# Arduino-RedBoard_new.net
KiCad netlist of a schematic drawn in Altium Designer
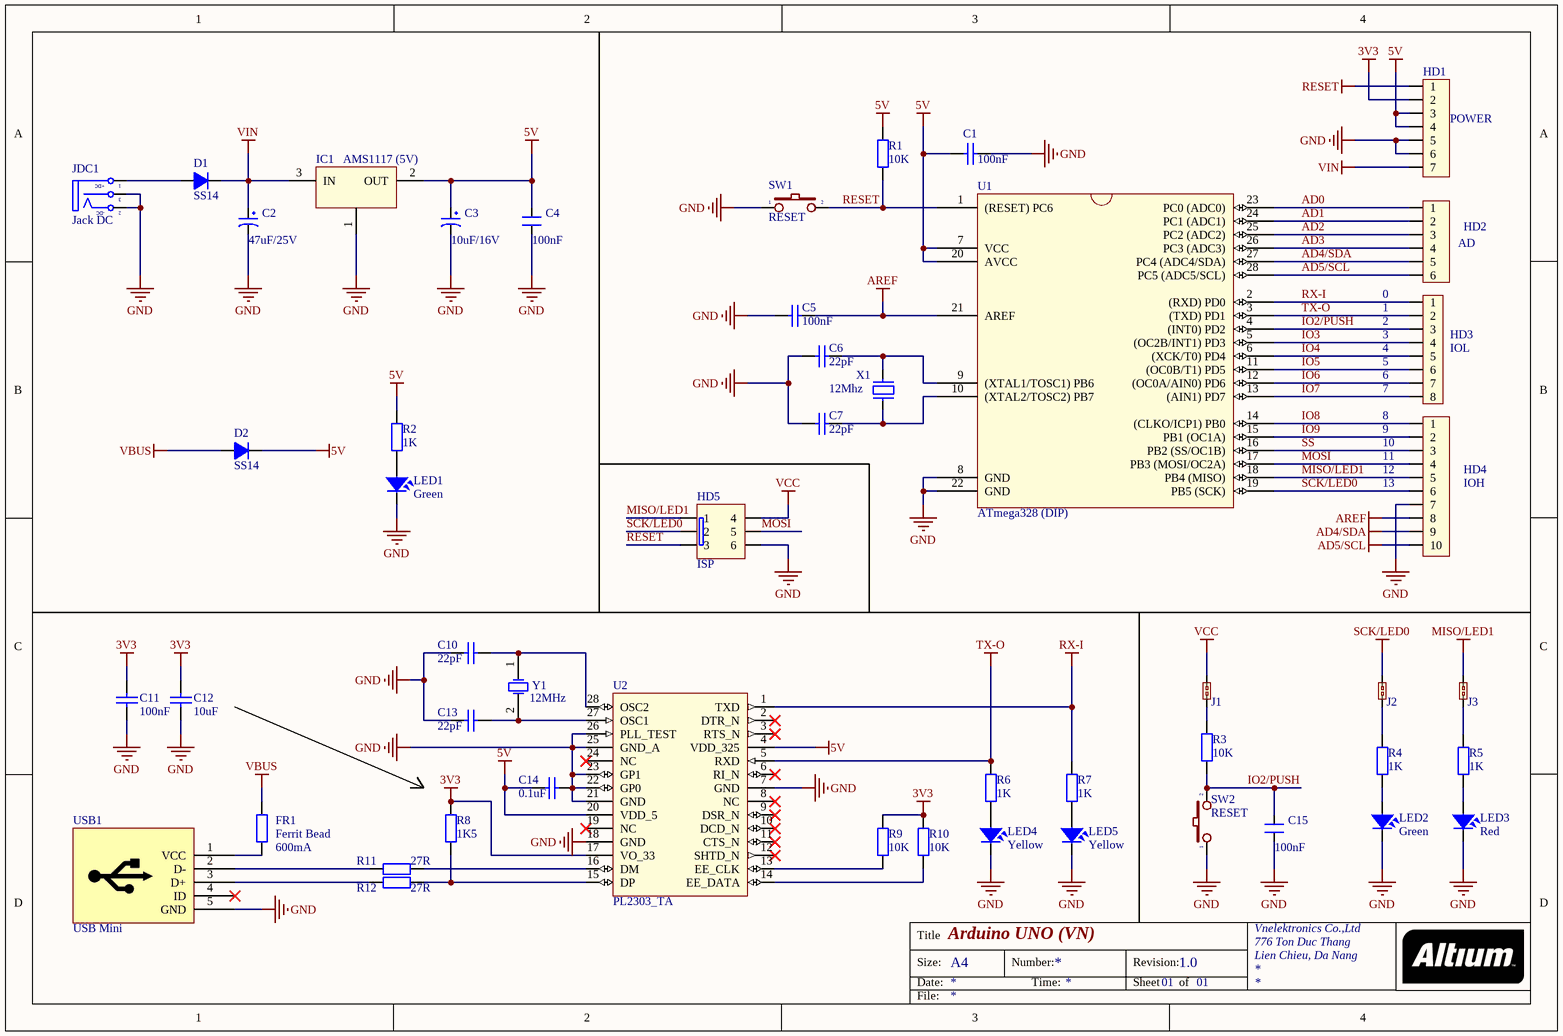
[diagram p0: Arduino-RedBoard_new.schdoc]

(export (version "E")
  (design (tool "Eeschema 10.0.6"))
  (components
    (comp (ref "C1")
      (value "100nF")
      (footprint "C0603")
      (description "CAP NPO CAPNTO 1nF 100V 10%")
      (fields (field (name "Comment") "5AK102KABAA"))
      (libsource (lib "lpson") (part "5AK102KABAA"))
    )
    (comp (ref "C2") (value "47uF/25V") (footprint "C_FK_47UF_25V") (libsource (lib "VNELEK") (part "CP1")))
    (comp (ref "C3")
      (value "10uF/16V")
      (footprint "C0805")
      (description "Cap P  0,1uF < 22uF , 16 - 50V")
      (libsource (lib "VNELEK") (part "CP1"))
    )
    (comp (ref "C4")
      (value "100nF")
      (footprint "C0603")
      (description "Cap np 104 => 105pF")
      (libsource (lib "VNELEK") (part "CN2"))
    )
    (comp (ref "C5")
      (value "100nF")
      (footprint "C0603")
      (description "CAP NPO CAPNTO 1nF 100V 10%")
      (fields (field (name "Comment") "5AK102KABAA"))
      (libsource (lib "lpson") (part "5AK102KABAA"))
    )
    (comp (ref "C6")
      (value "22pF")
      (footprint "C0603")
      (description "CAP NPO CAPNTO 1nF 100V 10%")
      (fields (field (name "Comment") "5AK102KABAA"))
      (libsource (lib "lpson") (part "5AK102KABAA"))
    )
    (comp (ref "C7")
      (value "22pF")
      (footprint "C0603")
      (description "CAP NPO CAPNTO 1nF 100V 10%")
      (fields (field (name "Comment") "5AK102KABAA"))
      (libsource (lib "lpson") (part "5AK102KABAA"))
    )
    (comp (ref "C10")
      (value "22pF")
      (footprint "C0603")
      (description "22pF/50V ±5% NPO SMD-0603 Capacitor")
      (fields (field (name "Comment") "CC0603JRNPO9BN") (field (name "PUBLISHER") "Altium Limited"))
      (libsource (lib "Miscellaneous Devices") (part "Cap"))
    )
    (comp (ref "C11")
      (value "100nF")
      (footprint "C0603")
      (description "100nF/50V ±10% X7R SMD-0603 Capacitor")
      (fields (field (name "Comment") "CC0603JRNPO9BN") (field (name "PUBLISHER") "Altium Limited"))
      (libsource (lib "Miscellaneous Devices") (part "Cap"))
    )
    (comp (ref "C12")
      (value "10uF")
      (footprint "C0805")
      (description "10uF/16V ±10% X7R SMD-0805 Capacitor")
      (fields (field (name "Comment") "C0805KRX7R7BB") (field (name "PUBLISHER") "Altium Limited"))
      (libsource (lib "Miscellaneous Devices") (part "Cap"))
    )
    (comp (ref "C13")
      (value "22pF")
      (footprint "C0603")
      (description "22pF/50V ±5% NPO SMD-0603 Capacitor")
      (fields (field (name "Comment") "CC0603JRNPO9BN") (field (name "PUBLISHER") "Altium Limited"))
      (libsource (lib "Miscellaneous Devices") (part "Cap"))
    )
    (comp (ref "C14")
      (value "0.1uF")
      (footprint "C0603")
      (description "100nF/50V ±10% X7R SMD-0603 Capacitor")
      (fields (field (name "Comment") "CC0603JRNPO9BN") (field (name "PUBLISHER") "Altium Limited"))
      (libsource (lib "Miscellaneous Devices") (part "Cap"))
    )
    (comp (ref "C15")
      (value "100nF")
      (footprint "C0603")
      (description "Cap np 104 => 105pF")
      (libsource (lib "VNELEK") (part "CN2"))
    )
    (comp (ref "D1")
      (value "SS14")
      (footprint "SS14")
      (description "Diode 1A")
      (libsource (lib "VNELEK") (part "D1A"))
    )
    (comp (ref "D2")
      (value "SS14")
      (footprint "SS14")
      (description "Diode 1A")
      (libsource (lib "VNELEK") (part "D1A"))
    )
    (comp (ref "FR1")
      (value "Ferrit Bead")
      (footprint "CB2012")
      (fields (field (name "ALTIUM_VALUE") "600mA"))
      (libsource (lib "Miscellaneous Devices") (part "Res2"))
    )
    (comp (ref "HD1")
      (value "POWER")
      (footprint "Header_7")
      (description "Header 7")
      (libsource (lib "Tran Tuan") (part "Hed7"))
    )
    (comp (ref "HD2")
      (value "AD")
      (footprint "Header_6")
      (description "Header 6")
      (libsource (lib "Tran Tuan") (part "Hed6"))
    )
    (comp (ref "HD3")
      (value "IOL")
      (footprint "Header_8")
      (description "Hedear 8")
      (fields (field (name "CREAT BY") "VanDungEvn@Gmail.com"))
      (libsource (lib "VNELEK") (part "Hed8"))
    )
    (comp (ref "HD4")
      (value "IOH")
      (footprint "Header_10")
      (description "Header 10")
      (libsource (lib "Tran Tuan") (part "Hed10"))
    )
    (comp (ref "HD5")
      (value "ISP")
      (footprint "Header_3x2")
      (description "Header 3x2")
      (libsource (lib "Tran Tuan") (part "HED3x2"))
    )
    (comp (ref "IC1")
      (value "AMS1117 (5V)")
      (footprint "AMS1117-5.0V")
      (description "1A LOW DROPOUT VOLTAGE REGULATOR")
      (libsource (lib "Tran Tuan") (part "AMS1117"))
    )
    (comp (ref "J1")
      (value "Short Jump")
      (footprint "Header_2")
      (libsource (lib "Tran Tuan") (part "ShortJump"))
    )
    (comp (ref "J2")
      (value "Short Jump")
      (footprint "Header_2")
      (libsource (lib "Tran Tuan") (part "ShortJump"))
    )
    (comp (ref "J3")
      (value "Short Jump")
      (footprint "Header_2")
      (libsource (lib "Tran Tuan") (part "ShortJump"))
    )
    (comp (ref "JDC1")
      (value "Jack DC")
      (footprint "DC-IN")
      (description "Jac DC input")
      (libsource (lib "VNELEK") (part "DCIN"))
    )
    (comp (ref "LED1")
      (value "Green")
      (footprint "Led 0805Y")
      (description "LED Single colour Green and Red")
      (libsource (lib "VNELEK") (part "LED"))
    )
    (comp (ref "LED2")
      (value "Green")
      (footprint "Led 0805G")
      (description "LED Single colour Green and Red")
      (libsource (lib "VNELEK") (part "LED"))
    )
    (comp (ref "LED3")
      (value "Red")
      (footprint "Led 0805R")
      (description "LED Single colour Green and Red")
      (libsource (lib "VNELEK") (part "LED"))
    )
    (comp (ref "LED4")
      (value "Yellow")
      (footprint "Led 0805G")
      (description "LED Single colour Green and Red")
      (libsource (lib "VNELEK") (part "LED"))
    )
    (comp (ref "LED5")
      (value "Yellow")
      (footprint "Led 0805R")
      (description "LED Single colour Green and Red")
      (libsource (lib "VNELEK") (part "LED"))
    )
    (comp (ref "R1")
      (value "10K")
      (footprint "RESC2012L")
      (description "Resistor")
      (fields (field (name "Comment") "Res2") (field (name "PUBLISHER") "Altium Limited"))
      (libsource (lib "Miscellaneous Devices") (part "Res2"))
    )
    (comp (ref "R2")
      (value "1K")
      (footprint "RESC2012L")
      (description "Resistor")
      (fields (field (name "Comment") "Res2") (field (name "PUBLISHER") "Altium Limited"))
      (libsource (lib "Miscellaneous Devices") (part "Res2"))
    )
    (comp (ref "R3")
      (value "10K")
      (footprint "RM06JTN (0603)")
      (description "Resistor")
      (fields (field (name "Comment") "Res2") (field (name "PUBLISHER") "Altium Limited"))
      (libsource (lib "Miscellaneous Devices") (part "Res2"))
    )
    (comp (ref "R4")
      (value "1K")
      (footprint "RM06JTN (0603)")
      (description "Resistor")
      (fields (field (name "Comment") "Res2") (field (name "PUBLISHER") "Altium Limited"))
      (libsource (lib "Miscellaneous Devices") (part "Res2"))
    )
    (comp (ref "R5")
      (value "1K")
      (footprint "RM06JTN (0603)")
      (description "Resistor")
      (fields (field (name "Comment") "Res2") (field (name "PUBLISHER") "Altium Limited"))
      (libsource (lib "Miscellaneous Devices") (part "Res2"))
    )
    (comp (ref "R6")
      (value "1K")
      (footprint "RM06JTN (0603)")
      (description "Resistor")
      (fields (field (name "Comment") "Res2") (field (name "PUBLISHER") "Altium Limited"))
      (libsource (lib "Miscellaneous Devices") (part "Res2"))
    )
    (comp (ref "R7")
      (value "1K")
      (footprint "RM06JTN (0603)")
      (description "Resistor")
      (fields (field (name "Comment") "Res2") (field (name "PUBLISHER") "Altium Limited"))
      (libsource (lib "Miscellaneous Devices") (part "Res2"))
    )
    (comp (ref "R8")
      (value "1K5")
      (footprint "RM06JTN (0603)")
      (description "1.5K ±5% SMD-0603 Resistor")
      (fields (field (name "Comment") "RM06JTN") (field (name "PUBLISHER") "Altium Limited"))
      (libsource (lib "") (part "Res2_2"))
    )
    (comp (ref "R9")
      (value "10K")
      (footprint "RM06JTN (0603)")
      (description "10K ±5% SMD-0603 Resistor")
      (fields (field (name "Comment") "RM06JTN") (field (name "PUBLISHER") "Altium Limited"))
      (libsource (lib "") (part "Res2_1"))
    )
    (comp (ref "R10")
      (value "10K")
      (footprint "RM06JTN (0603)")
      (description "10K ±5% SMD-0603 Resistor")
      (fields (field (name "Comment") "RM06JTN") (field (name "PUBLISHER") "Altium Limited"))
      (libsource (lib "") (part "Res2_1"))
    )
    (comp (ref "R11")
      (value "27R")
      (footprint "RM06JTN (0603)")
      (description "Resistor")
      (fields (field (name "Comment") "Res2") (field (name "PUBLISHER") "Altium Limited"))
      (libsource (lib "") (part "Res2_1"))
    )
    (comp (ref "R12")
      (value "27R")
      (footprint "RM06JTN (0603)")
      (description "Resistor")
      (fields (field (name "Comment") "Res2") (field (name "PUBLISHER") "Altium Limited"))
      (libsource (lib "") (part "Res2_1"))
    )
    (comp (ref "SW1")
      (value "RESET")
      (footprint "BUTTON 2PIN TRON")
      (description "Switch button 2 pin")
      (libsource (lib "VNELEK") (part "SW2"))
    )
    (comp (ref "SW2")
      (value "RESET")
      (footprint "BUTTON 2PIN TRON")
      (description "Switch button 2 pin")
      (libsource (lib "VNELEK") (part "SW2"))
    )
    (comp (ref "U1")
      (value "ATmega328 (DIP)")
      (footprint "ATmega328 (DIP)")
      (description "Atmel 8-bit Microcontroller")
      (libsource (lib "Tran Tuan") (part "ATmega328_1"))
    )
    (comp (ref "U2")
      (value "PL2303_TA")
      (footprint "PL2303HX")
      (description "USB to UART,28pin,EEPROM extract")
      (libsource (lib "PL2303HXA") (part "PL2303_HXA"))
    )
    (comp (ref "USB1") (value "USB Mini") (footprint "USBMNIB") (libsource (lib "VNELEK") (part "USB_M")))
    (comp (ref "X1")
      (value "12Mhz")
      (footprint "CRYSTAL")
      (description "Crystal For all Crystal 2pin.")
      (libsource (lib "lpson") (part "XT2"))
    )
    (comp (ref "Y1")
      (value "12MHz")
      (footprint "CSTCE16M0V53-R0")
      (description "12MHz-HC49S,crytal holes")
      (fields (field (name "PUBLISHER") "Altium Limited"))
      (libsource (lib "Miscellaneous Devices") (part "XTAL"))
    )
  )
  (nets
    (net (code "1") (name "/AD0") (class "Default")
      (node (ref "HD2") (pin "1") (pinfunction "1_1") (pintype "passive"))
      (node (ref "U1") (pin "23") (pinfunction "PC0_(ADC0)_23") (pintype "bidirectional"))
    )
    (net (code "2") (name "/AD1") (class "Default")
      (node (ref "HD2") (pin "2") (pinfunction "2_2") (pintype "passive"))
      (node (ref "U1") (pin "24") (pinfunction "PC1_(ADC1)_24") (pintype "bidirectional"))
    )
    (net (code "3") (name "/AD2") (class "Default")
      (node (ref "HD2") (pin "3") (pinfunction "3_3") (pintype "passive"))
      (node (ref "U1") (pin "25") (pinfunction "PC2_(ADC2)_25") (pintype "bidirectional"))
    )
    (net (code "4") (name "/AD3") (class "Default")
      (node (ref "HD2") (pin "4") (pinfunction "4_4") (pintype "passive"))
      (node (ref "U1") (pin "26") (pinfunction "PC3_(ADC3)_26") (pintype "bidirectional"))
    )
    (net (code "5") (name "/IO2{slash}PUSH") (class "Default")
      (node (ref "C15") (pin "2") (pinfunction "2_2") (pintype "passive"))
      (node (ref "HD3") (pin "3") (pinfunction "3_3") (pintype "passive"))
      (node (ref "R3") (pin "1") (pinfunction "1_1") (pintype "passive"))
      (node (ref "SW2") (pin "2") (pinfunction "2_2") (pintype "passive"))
      (node (ref "U1") (pin "4") (pinfunction "(INT0)_PD2_4") (pintype "bidirectional"))
    )
    (net (code "6") (name "/IO3") (class "Default")
      (node (ref "HD3") (pin "4") (pinfunction "4_4") (pintype "passive"))
      (node (ref "U1") (pin "5") (pinfunction "(OC2B/INT1)_PD3_5") (pintype "bidirectional"))
    )
    (net (code "7") (name "/IO4") (class "Default")
      (node (ref "HD3") (pin "5") (pinfunction "5_5") (pintype "passive"))
      (node (ref "U1") (pin "6") (pinfunction "(XCK/T0)_PD4_6") (pintype "bidirectional"))
    )
    (net (code "8") (name "/IO5") (class "Default")
      (node (ref "HD3") (pin "6") (pinfunction "6_6") (pintype "passive"))
      (node (ref "U1") (pin "11") (pinfunction "(OC0B/T1)_PD5_11") (pintype "bidirectional"))
    )
    (net (code "9") (name "/IO6") (class "Default")
      (node (ref "HD3") (pin "7") (pinfunction "7_7") (pintype "passive"))
      (node (ref "U1") (pin "12") (pinfunction "(OC0A/AIN0)_PD6_12") (pintype "bidirectional"))
    )
    (net (code "10") (name "/IO7") (class "Default")
      (node (ref "HD3") (pin "8") (pinfunction "8_8") (pintype "passive"))
      (node (ref "U1") (pin "13") (pinfunction "(AIN1)_PD7_13") (pintype "bidirectional"))
    )
    (net (code "11") (name "/IO8") (class "Default")
      (node (ref "HD4") (pin "1") (pinfunction "1_1") (pintype "passive"))
      (node (ref "U1") (pin "14") (pinfunction "(CLKO/ICP1)_PB0_14") (pintype "bidirectional"))
    )
    (net (code "12") (name "/IO9") (class "Default")
      (node (ref "HD4") (pin "2") (pinfunction "2_2") (pintype "passive"))
      (node (ref "U1") (pin "15") (pinfunction "PB1_(OC1A)_15") (pintype "bidirectional"))
    )
    (net (code "13") (name "/MOSI") (class "Default")
      (node (ref "HD4") (pin "4") (pinfunction "4_4") (pintype "passive"))
      (node (ref "HD5") (pin "5") (pinfunction "5_5") (pintype "passive"))
      (node (ref "U1") (pin "17") (pinfunction "PB3_(MOSI/OC2A)_17") (pintype "bidirectional"))
    )
    (net (code "14") (name "/SS") (class "Default")
      (node (ref "HD4") (pin "3") (pinfunction "3_3") (pintype "passive"))
      (node (ref "U1") (pin "16") (pinfunction "PB2_(SS/OC1B)_16") (pintype "bidirectional"))
    )
    (net (code "15") (name "3V3") (class "Default")
      (node (ref "C11") (pin "2") (pinfunction "2_2") (pintype "passive"))
      (node (ref "C12") (pin "1") (pinfunction "1_1") (pintype "passive"))
      (node (ref "HD1") (pin "2") (pinfunction "2_2") (pintype "passive"))
      (node (ref "R10") (pin "1") (pinfunction "1_1") (pintype "passive"))
      (node (ref "R8") (pin "1") (pinfunction "1_1") (pintype "passive"))
      (node (ref "R9") (pin "1") (pinfunction "1_1") (pintype "passive"))
      (node (ref "U2") (pin "17") (pinfunction "VO_33_17") (pintype "passive"))
    )
    (net (code "16") (name "5V") (class "Default")
      (node (ref "C1") (pin "2") (pinfunction "2_2") (pintype "passive"))
      (node (ref "C14") (pin "1") (pinfunction "1_1") (pintype "passive"))
      (node (ref "C3") (pin "1") (pinfunction "1_1") (pintype "passive"))
      (node (ref "C4") (pin "2") (pinfunction "2_2") (pintype "passive"))
      (node (ref "D2") (pin "2") (pinfunction "K_2") (pintype "passive"))
      (node (ref "HD1") (pin "3") (pinfunction "3_3") (pintype "passive"))
      (node (ref "HD1") (pin "4") (pinfunction "4_4") (pintype "passive"))
      (node (ref "IC1") (pin "2") (pinfunction "OUT_2") (pintype "passive"))
      (node (ref "R1") (pin "2") (pinfunction "2_2") (pintype "passive"))
      (node (ref "R2") (pin "2") (pinfunction "2_2") (pintype "passive"))
      (node (ref "U1") (pin "20") (pinfunction "AVCC_20") (pintype "passive"))
      (node (ref "U1") (pin "7") (pinfunction "VCC_7") (pintype "passive"))
      (node (ref "U2") (pin "20") (pinfunction "VDD_5_20") (pintype "passive"))
      (node (ref "U2") (pin "4") (pinfunction "VDD_325_4") (pintype "passive"))
    )
    (net (code "17") (name "AD4{slash}SDA") (class "Default")
      (node (ref "HD2") (pin "5") (pinfunction "5_5") (pintype "passive"))
      (node (ref "HD4") (pin "9") (pinfunction "9_9") (pintype "passive"))
      (node (ref "U1") (pin "27") (pinfunction "PC4_(ADC4/SDA)_27") (pintype "bidirectional"))
    )
    (net (code "18") (name "AD5{slash}SCL") (class "Default")
      (node (ref "HD2") (pin "6") (pinfunction "6_6") (pintype "passive"))
      (node (ref "HD4") (pin "10") (pinfunction "10_10") (pintype "passive"))
      (node (ref "U1") (pin "28") (pinfunction "PC5_(ADC5/SCL)_28") (pintype "bidirectional"))
    )
    (net (code "19") (name "AREF") (class "Default")
      (node (ref "C5") (pin "2") (pinfunction "2_2") (pintype "passive"))
      (node (ref "HD4") (pin "8") (pinfunction "8_8") (pintype "passive"))
      (node (ref "U1") (pin "21") (pinfunction "AREF_21") (pintype "passive"))
    )
    (net (code "20") (name "GND") (class "Default")
      (node (ref "C1") (pin "1") (pinfunction "1_1") (pintype "passive"))
      (node (ref "C10") (pin "1") (pinfunction "1_1") (pintype "passive"))
      (node (ref "C11") (pin "1") (pinfunction "1_1") (pintype "passive"))
      (node (ref "C12") (pin "2") (pinfunction "2_2") (pintype "passive"))
      (node (ref "C13") (pin "1") (pinfunction "1_1") (pintype "passive"))
      (node (ref "C14") (pin "2") (pinfunction "2_2") (pintype "passive"))
      (node (ref "C15") (pin "1") (pinfunction "1_1") (pintype "passive"))
      (node (ref "C2") (pin "2") (pinfunction "2_2") (pintype "passive"))
      (node (ref "C3") (pin "2") (pinfunction "2_2") (pintype "passive"))
      (node (ref "C4") (pin "1") (pinfunction "1_1") (pintype "passive"))
      (node (ref "C5") (pin "1") (pinfunction "1_1") (pintype "passive"))
      (node (ref "C6") (pin "1") (pinfunction "1_1") (pintype "passive"))
      (node (ref "C7") (pin "1") (pinfunction "1_1") (pintype "passive"))
      (node (ref "HD1") (pin "5") (pinfunction "5_5") (pintype "passive"))
      (node (ref "HD1") (pin "6") (pinfunction "6_6") (pintype "passive"))
      (node (ref "HD4") (pin "7") (pinfunction "7_7") (pintype "passive"))
      (node (ref "HD5") (pin "6") (pinfunction "6_6") (pintype "passive"))
      (node (ref "IC1") (pin "1") (pinfunction "GND_1") (pintype "passive"))
      (node (ref "JDC1") (pin "2") (pinfunction "TN_2") (pintype "passive"))
      (node (ref "JDC1") (pin "3") (pinfunction "S_3") (pintype "power_in"))
      (node (ref "LED1") (pin "2") (pinfunction "2_2") (pintype "passive"))
      (node (ref "LED2") (pin "2") (pinfunction "2_2") (pintype "passive"))
      (node (ref "LED3") (pin "2") (pinfunction "2_2") (pintype "passive"))
      (node (ref "LED4") (pin "2") (pinfunction "2_2") (pintype "passive"))
      (node (ref "LED5") (pin "2") (pinfunction "2_2") (pintype "passive"))
      (node (ref "SW1") (pin "1") (pinfunction "1_1") (pintype "passive"))
      (node (ref "SW2") (pin "1") (pinfunction "1_1") (pintype "passive"))
      (node (ref "U1") (pin "22") (pinfunction "GND_22") (pintype "passive"))
      (node (ref "U1") (pin "8") (pinfunction "GND_8") (pintype "passive"))
      (node (ref "U2") (pin "18") (pinfunction "GND_18") (pintype "passive"))
      (node (ref "U2") (pin "21") (pinfunction "GND_21") (pintype "passive"))
      (node (ref "U2") (pin "22") (pinfunction "GP0_22") (pintype "bidirectional"))
      (node (ref "U2") (pin "23") (pinfunction "GP1_23") (pintype "bidirectional"))
      (node (ref "U2") (pin "25") (pinfunction "GND_A_25") (pintype "passive"))
      (node (ref "U2") (pin "26") (pinfunction "PLL_TEST_26") (pintype "input"))
      (node (ref "U2") (pin "7") (pinfunction "GND_7") (pintype "passive"))
      (node (ref "USB1") (pin "5") (pinfunction "GND_5") (pintype "passive"))
    )
    (net (code "21") (name "MISO{slash}LED1") (class "Default")
      (node (ref "HD4") (pin "5") (pinfunction "5_5") (pintype "passive"))
      (node (ref "HD5") (pin "1") (pinfunction "1_1") (pintype "passive"))
      (node (ref "J3") (pin "2") (pinfunction "2_2") (pintype "passive"))
      (node (ref "U1") (pin "18") (pinfunction "PB4_(MISO)_18") (pintype "bidirectional"))
    )
    (net (code "22") (name "Net-(D1-A)") (class "Default")
      (node (ref "D1") (pin "1") (pinfunction "A_1") (pintype "passive"))
      (node (ref "JDC1") (pin "1") (pinfunction "T_1") (pintype "passive"))
    )
    (net (code "23") (name "Net-(J1-Pad1)") (class "Default")
      (node (ref "J1") (pin "1") (pinfunction "1_1") (pintype "passive"))
      (node (ref "R3") (pin "2") (pinfunction "2_2") (pintype "passive"))
    )
    (net (code "24") (name "Net-(J2-Pad1)") (class "Default")
      (node (ref "J2") (pin "1") (pinfunction "1_1") (pintype "passive"))
      (node (ref "R4") (pin "2") (pinfunction "2_2") (pintype "passive"))
    )
    (net (code "25") (name "Net-(J3-Pad1)") (class "Default")
      (node (ref "J3") (pin "1") (pinfunction "1_1") (pintype "passive"))
      (node (ref "R5") (pin "2") (pinfunction "2_2") (pintype "passive"))
    )
    (net (code "26") (name "Net-(LED1-Pad1)") (class "Default")
      (node (ref "LED1") (pin "1") (pinfunction "1_1") (pintype "passive"))
      (node (ref "R2") (pin "1") (pinfunction "1_1") (pintype "passive"))
    )
    (net (code "27") (name "Net-(LED2-Pad1)") (class "Default")
      (node (ref "LED2") (pin "1") (pinfunction "1_1") (pintype "passive"))
      (node (ref "R4") (pin "1") (pinfunction "1_1") (pintype "passive"))
    )
    (net (code "28") (name "Net-(LED3-Pad1)") (class "Default")
      (node (ref "LED3") (pin "1") (pinfunction "1_1") (pintype "passive"))
      (node (ref "R5") (pin "1") (pinfunction "1_1") (pintype "passive"))
    )
    (net (code "29") (name "Net-(LED4-Pad1)") (class "Default")
      (node (ref "LED4") (pin "1") (pinfunction "1_1") (pintype "passive"))
      (node (ref "R6") (pin "1") (pinfunction "1_1") (pintype "passive"))
    )
    (net (code "30") (name "Net-(LED5-Pad1)") (class "Default")
      (node (ref "LED5") (pin "1") (pinfunction "1_1") (pintype "passive"))
      (node (ref "R7") (pin "1") (pinfunction "1_1") (pintype "passive"))
    )
    (net (code "31") (name "Net-(U1-(XTAL1{slash}TOSC1)_PB6)") (class "Default")
      (node (ref "C6") (pin "2") (pinfunction "2_2") (pintype "passive"))
      (node (ref "U1") (pin "9") (pinfunction "(XTAL1/TOSC1)_PB6_9") (pintype "passive"))
      (node (ref "X1") (pin "2") (pinfunction "2_2") (pintype "passive"))
    )
    (net (code "32") (name "Net-(U1-(XTAL2{slash}TOSC2)_PB7)") (class "Default")
      (node (ref "C7") (pin "2") (pinfunction "2_2") (pintype "passive"))
      (node (ref "U1") (pin "10") (pinfunction "(XTAL2/TOSC2)_PB7_10") (pintype "passive"))
      (node (ref "X1") (pin "1") (pinfunction "1_1") (pintype "passive"))
    )
    (net (code "33") (name "Net-(U2-DM)") (class "Default")
      (node (ref "R11") (pin "1") (pinfunction "1_1") (pintype "passive"))
      (node (ref "U2") (pin "16") (pinfunction "DM_16") (pintype "bidirectional"))
    )
    (net (code "34") (name "Net-(U2-DP)") (class "Default")
      (node (ref "R12") (pin "1") (pinfunction "1_1") (pintype "passive"))
      (node (ref "R8") (pin "2") (pinfunction "2_2") (pintype "passive"))
      (node (ref "U2") (pin "15") (pinfunction "DP_15") (pintype "bidirectional"))
    )
    (net (code "35") (name "Net-(U2-EE_CLK)") (class "Default")
      (node (ref "R9") (pin "2") (pinfunction "2_2") (pintype "passive"))
      (node (ref "U2") (pin "13") (pinfunction "EE_CLK_13") (pintype "bidirectional"))
    )
    (net (code "36") (name "Net-(U2-EE_DATA)") (class "Default")
      (node (ref "R10") (pin "2") (pinfunction "2_2") (pintype "passive"))
      (node (ref "U2") (pin "14") (pinfunction "EE_DATA_14") (pintype "bidirectional"))
    )
    (net (code "37") (name "Net-(U2-OSC1)") (class "Default")
      (node (ref "C13") (pin "2") (pinfunction "2_2") (pintype "passive"))
      (node (ref "U2") (pin "27") (pinfunction "OSC1_27") (pintype "input"))
      (node (ref "Y1") (pin "2") (pinfunction "OSC2_2") (pintype "passive"))
    )
    (net (code "38") (name "Net-(U2-OSC2)") (class "Default")
      (node (ref "C10") (pin "2") (pinfunction "2_2") (pintype "passive"))
      (node (ref "U2") (pin "28") (pinfunction "OSC2_28") (pintype "bidirectional"))
      (node (ref "Y1") (pin "1") (pinfunction "OSC1_1") (pintype "passive"))
    )
    (net (code "39") (name "Net-(USB1-D+)") (class "Default")
      (node (ref "R12") (pin "2") (pinfunction "2_2") (pintype "passive"))
      (node (ref "USB1") (pin "3") (pinfunction "D+_3") (pintype "passive"))
    )
    (net (code "40") (name "Net-(USB1-D-)") (class "Default")
      (node (ref "R11") (pin "2") (pinfunction "2_2") (pintype "passive"))
      (node (ref "USB1") (pin "2") (pinfunction "D-_2") (pintype "passive"))
    )
    (net (code "41") (name "Net-(USB1-VCC)") (class "Default")
      (node (ref "FR1") (pin "1") (pinfunction "1_1") (pintype "passive"))
      (node (ref "USB1") (pin "1") (pinfunction "VCC_1") (pintype "passive"))
    )
    (net (code "42") (name "RESET") (class "Default")
      (node (ref "HD1") (pin "1") (pinfunction "1_1") (pintype "passive"))
      (node (ref "HD5") (pin "3") (pinfunction "3_3") (pintype "passive"))
      (node (ref "R1") (pin "1") (pinfunction "1_1") (pintype "passive"))
      (node (ref "SW1") (pin "2") (pinfunction "2_2") (pintype "passive"))
      (node (ref "U1") (pin "1") (pinfunction "(RESET)_PC6_1") (pintype "passive"))
    )
    (net (code "43") (name "RX-I") (class "Default")
      (node (ref "HD3") (pin "1") (pinfunction "1_1") (pintype "passive"))
      (node (ref "R7") (pin "2") (pinfunction "2_2") (pintype "passive"))
      (node (ref "U1") (pin "2") (pinfunction "(RXD)_PD0_2") (pintype "bidirectional"))
      (node (ref "U2") (pin "1") (pinfunction "TXD_1") (pintype "output"))
    )
    (net (code "44") (name "SCK{slash}LED0") (class "Default")
      (node (ref "HD4") (pin "6") (pinfunction "6_6") (pintype "passive"))
      (node (ref "HD5") (pin "2") (pinfunction "2_2") (pintype "passive"))
      (node (ref "J2") (pin "2") (pinfunction "2_2") (pintype "passive"))
      (node (ref "U1") (pin "19") (pinfunction "PB5_(SCK)_19") (pintype "bidirectional"))
    )
    (net (code "45") (name "TX-O") (class "Default")
      (node (ref "HD3") (pin "2") (pinfunction "2_2") (pintype "passive"))
      (node (ref "R6") (pin "2") (pinfunction "2_2") (pintype "passive"))
      (node (ref "U1") (pin "3") (pinfunction "(TXD)_PD1_3") (pintype "bidirectional"))
      (node (ref "U2") (pin "5") (pinfunction "RXD_5") (pintype "input"))
    )
    (net (code "46") (name "VBUS") (class "Default")
      (node (ref "D2") (pin "1") (pinfunction "A_1") (pintype "passive"))
      (node (ref "FR1") (pin "2") (pinfunction "2_2") (pintype "passive"))
    )
    (net (code "47") (name "VCC") (class "Default")
      (node (ref "HD5") (pin "4") (pinfunction "4_4") (pintype "passive"))
      (node (ref "J1") (pin "2") (pinfunction "2_2") (pintype "passive"))
    )
    (net (code "48") (name "VIN") (class "Default")
      (node (ref "C2") (pin "1") (pinfunction "1_1") (pintype "passive"))
      (node (ref "D1") (pin "2") (pinfunction "K_2") (pintype "passive"))
      (node (ref "HD1") (pin "7") (pinfunction "7_7") (pintype "passive"))
      (node (ref "IC1") (pin "3") (pinfunction "IN_3") (pintype "passive"))
    )
    (net (code "49") (name "unconnected-(U2-CTS_N-Pad11)") (class "Default")
      (node (ref "U2") (pin "11") (pinfunction "CTS_N_11") (pintype "bidirectional+no_connect"))
    )
    (net (code "50") (name "unconnected-(U2-DCD_N-Pad10)") (class "Default")
      (node (ref "U2") (pin "10") (pinfunction "DCD_N_10") (pintype "bidirectional+no_connect"))
    )
    (net (code "51") (name "unconnected-(U2-DSR_N-Pad9)") (class "Default")
      (node (ref "U2") (pin "9") (pinfunction "DSR_N_9") (pintype "bidirectional+no_connect"))
    )
    (net (code "52") (name "unconnected-(U2-DTR_N-Pad2)") (class "Default")
      (node (ref "U2") (pin "2") (pinfunction "DTR_N_2") (pintype "output+no_connect"))
    )
    (net (code "53") (name "unconnected-(U2-NC-Pad8)") (class "Default")
      (node (ref "U2") (pin "8") (pinfunction "NC_8") (pintype "passive+no_connect"))
    )
    (net (code "54") (name "unconnected-(U2-NC-Pad19)") (class "Default")
      (node (ref "U2") (pin "19") (pinfunction "NC_19") (pintype "passive+no_connect"))
    )
    (net (code "55") (name "unconnected-(U2-NC-Pad24)") (class "Default")
      (node (ref "U2") (pin "24") (pinfunction "NC_24") (pintype "passive+no_connect"))
    )
    (net (code "56") (name "unconnected-(U2-RI_N-Pad6)") (class "Default")
      (node (ref "U2") (pin "6") (pinfunction "RI_N_6") (pintype "bidirectional+no_connect"))
    )
    (net (code "57") (name "unconnected-(U2-RTS_N-Pad3)") (class "Default")
      (node (ref "U2") (pin "3") (pinfunction "RTS_N_3") (pintype "output+no_connect"))
    )
    (net (code "58") (name "unconnected-(U2-SHTD_N-Pad12)") (class "Default")
      (node (ref "U2") (pin "12") (pinfunction "SHTD_N_12") (pintype "output+no_connect"))
    )
    (net (code "59") (name "unconnected-(USB1-ID-Pad4)") (class "Default")
      (node (ref "USB1") (pin "4") (pinfunction "ID_4") (pintype "passive+no_connect"))
    )
  )
)
